# PowerAmplifier_BFU590G.net
KiCad netlist of a schematic drawn in Altium Designer
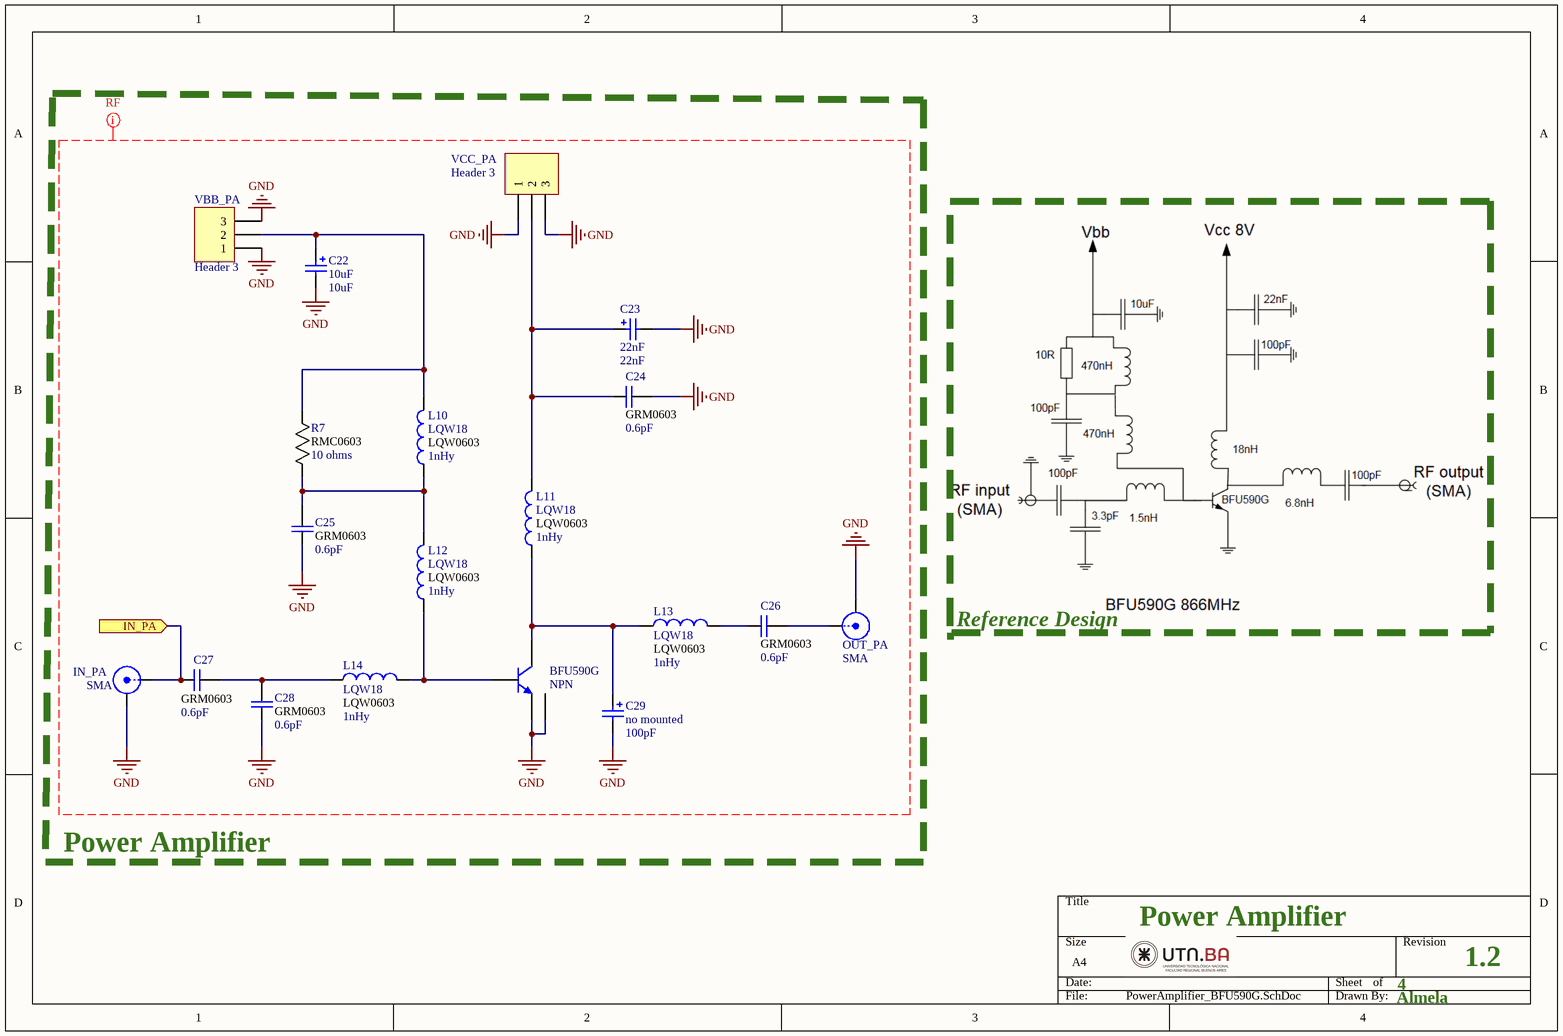
[diagram p0: PowerAmplifier_BFU590G.SchDoc]

(export (version "E")
  (design (tool "Eeschema 10.0.6"))
  (components
    (comp (ref "BFU590G")
      (value "NPN")
      (footprint "SOT223_L")
      (description "NPN Bipolar Transistor")
      (fields (field (name "PUBLISHER") "Altium Limited"))
      (libsource (lib "Radar_RF_EAIII") (part "BFU590G"))
    )
    (comp (ref "C22")
      (value "10uF")
      (footprint "6-0805_N")
      (description "Polarized Capacitor (Axial)")
      (fields (field (name "ALTIUM_VALUE") "10uF") (field (name "PUBLISHER") "Altium Limited"))
      (libsource (lib "Radar_RF_EAIII") (part "Cap Pol2_7"))
    )
    (comp (ref "C23")
      (value "22nF")
      (footprint "6-0805_N")
      (description "Polarized Capacitor (Axial)")
      (fields (field (name "ALTIUM_VALUE") "22nF") (field (name "PUBLISHER") "Altium Limited"))
      (libsource (lib "PCB_Project") (part "Cap Pol2_1"))
    )
    (comp (ref "C24")
      (value "0.6pF")
      (footprint "GRM0603")
      (description "Capacitor GRM18 0603")
      (fields (field (name "Comment") "Cap 0603") (field (name "PUBLISHER") "Altium Limited"))
      (libsource (lib "Radar_RF_EAIII") (part "Cap"))
    )
    (comp (ref "C25")
      (value "0.6pF")
      (footprint "GRM0603")
      (description "Capacitor GRM18 0603")
      (fields (field (name "Comment") "Cap 0603") (field (name "PUBLISHER") "Altium Limited"))
      (libsource (lib "Radar_RF_EAIII") (part "Cap"))
    )
    (comp (ref "C26")
      (value "0.6pF")
      (footprint "GRM0603")
      (description "Capacitor GRM18 0603")
      (fields (field (name "Comment") "Cap 0603") (field (name "PUBLISHER") "Altium Limited"))
      (libsource (lib "Radar_RF_EAIII") (part "Cap"))
    )
    (comp (ref "C27")
      (value "0.6pF")
      (footprint "GRM0603")
      (description "Capacitor GRM18 0603")
      (fields (field (name "Comment") "Cap 0603") (field (name "PUBLISHER") "Altium Limited"))
      (libsource (lib "Radar_RF_EAIII") (part "Cap"))
    )
    (comp (ref "C28")
      (value "0.6pF")
      (footprint "GRM0603")
      (description "Capacitor GRM18 0603")
      (fields (field (name "Comment") "Cap 0603") (field (name "PUBLISHER") "Altium Limited"))
      (libsource (lib "Radar_RF_EAIII") (part "Cap"))
    )
    (comp (ref "C29")
      (value "no mounted")
      (footprint "6-0805_N")
      (description "Polarized Capacitor (Axial)")
      (fields (field (name "ALTIUM_VALUE") "100pF") (field (name "PUBLISHER") "Altium Limited"))
      (libsource (lib "PCB_Project") (part "Cap Pol2_1"))
    )
    (comp (ref "IN_PA")
      (value "SMA")
      (footprint "SMA-142-0701-851_V2")
      (description "SMA Straight Connector")
      (fields (field (name "PUBLISHER") "Altium Limited"))
      (libsource (lib "Radar_RF_EAIII") (part "SMA"))
    )
    (comp (ref "L10")
      (value "LQW18")
      (footprint "INDC1608X100N")
      (description "Ind RF Chip Wirewound 18nH 5% 100MHz 40Q-Factor 550mA 0603 Paper T/R")
      (fields
        (field (name "MP") "LQW18AN18NJ00D")
        (field (name "PARAMETER 1") "LQW0603")
        (field (name "ALTIUM_VALUE") "1nHy")
      )
      (libsource (lib "Radar_RF_EAIII") (part "LQW18"))
    )
    (comp (ref "L11")
      (value "LQW18")
      (footprint "INDC1608X100N")
      (description "Ind RF Chip Wirewound 18nH 5% 100MHz 40Q-Factor 550mA 0603 Paper T/R")
      (fields
        (field (name "MP") "LQW18AN18NJ00D")
        (field (name "PARAMETER 1") "LQW0603")
        (field (name "ALTIUM_VALUE") "1nHy")
      )
      (libsource (lib "Radar_RF_EAIII") (part "LQW18"))
    )
    (comp (ref "L12")
      (value "LQW18")
      (footprint "INDC1608X100N")
      (description "Ind RF Chip Wirewound 18nH 5% 100MHz 40Q-Factor 550mA 0603 Paper T/R")
      (fields
        (field (name "MP") "LQW18AN18NJ00D")
        (field (name "PARAMETER 1") "LQW0603")
        (field (name "ALTIUM_VALUE") "1nHy")
      )
      (libsource (lib "Radar_RF_EAIII") (part "LQW18"))
    )
    (comp (ref "L13")
      (value "LQW18")
      (footprint "INDC1608X100N")
      (description "Ind RF Chip Wirewound 18nH 5% 100MHz 40Q-Factor 550mA 0603 Paper T/R")
      (fields
        (field (name "MP") "LQW18AN18NJ00D")
        (field (name "PARAMETER 1") "LQW0603")
        (field (name "ALTIUM_VALUE") "1nHy")
      )
      (libsource (lib "Radar_RF_EAIII") (part "LQW18"))
    )
    (comp (ref "L14")
      (value "LQW18")
      (footprint "INDC1608X100N")
      (description "Ind RF Chip Wirewound 18nH 5% 100MHz 40Q-Factor 550mA 0603 Paper T/R")
      (fields
        (field (name "MP") "LQW18AN18NJ00D")
        (field (name "PARAMETER 1") "LQW0603")
        (field (name "ALTIUM_VALUE") "1nHy")
      )
      (libsource (lib "Radar_RF_EAIII") (part "LQW18"))
    )
    (comp (ref "OUT_PA")
      (value "SMA")
      (footprint "SMA-142-0701-851_V2")
      (description "SMA Straight Connector")
      (fields (field (name "PUBLISHER") "Altium Limited"))
      (libsource (lib "Radar_RF_EAIII") (part "SMA"))
    )
    (comp (ref "R7")
      (value "10 ohms")
      (footprint "RMC0603")
      (description "Resistor RMC0603")
      (fields (field (name "Comment") "Resistor"))
      (libsource (lib "Radar_RF_EAIII") (part "Resistor"))
    )
    (comp (ref "VBB_PA")
      (value "Header 3")
      (footprint "HDR1X3")
      (description "Header, 3-Pin")
      (fields (field (name "PUBLISHER") "Altium Limited"))
      (libsource (lib "") (part "Header 3_1"))
    )
    (comp (ref "VCC_PA")
      (value "Header 3")
      (footprint "HDR1X3")
      (description "Header, 3-Pin")
      (fields (field (name "PUBLISHER") "Altium Limited"))
      (libsource (lib "Miscellaneous Connectors") (part "Header 3"))
    )
  )
  (nets
    (net (code "1") (name "/IN_PA") (class "Default")
      (node (ref "C27") (pin "1") (pinfunction "1_1") (pintype "passive"))
      (node (ref "IN_PA") (pin "1") (pinfunction "X_1") (pintype "passive"))
    )
    (net (code "2") (name "GND") (class "Default")
      (node (ref "BFU590G") (pin "1") (pinfunction "E_1") (pintype "passive"))
      (node (ref "BFU590G") (pin "3") (pinfunction "E_3") (pintype "passive"))
      (node (ref "C22") (pin "2") (pinfunction "2_2") (pintype "passive"))
      (node (ref "C23") (pin "2") (pinfunction "2_2") (pintype "passive"))
      (node (ref "C24") (pin "2") (pinfunction "2_2") (pintype "passive"))
      (node (ref "C25") (pin "1") (pinfunction "1_1") (pintype "passive"))
      (node (ref "C28") (pin "1") (pinfunction "1_1") (pintype "passive"))
      (node (ref "C29") (pin "2") (pinfunction "2_2") (pintype "passive"))
      (node (ref "IN_PA") (pin "2") (pinfunction "Y_2") (pintype "passive"))
      (node (ref "OUT_PA") (pin "2") (pinfunction "Y_2") (pintype "passive"))
      (node (ref "VBB_PA") (pin "1") (pinfunction "1_1") (pintype "passive"))
      (node (ref "VBB_PA") (pin "3") (pinfunction "3_3") (pintype "passive"))
      (node (ref "VCC_PA") (pin "1") (pinfunction "1_1") (pintype "passive"))
      (node (ref "VCC_PA") (pin "3") (pinfunction "3_3") (pintype "passive"))
    )
    (net (code "3") (name "Net-(BFU590G-B)") (class "Default")
      (node (ref "BFU590G") (pin "2") (pinfunction "B_2") (pintype "passive"))
      (node (ref "L12") (pin "1") (pinfunction "1_1") (pintype "passive"))
      (node (ref "L14") (pin "2") (pinfunction "2_2") (pintype "passive"))
    )
    (net (code "4") (name "Net-(BFU590G-C)") (class "Default")
      (node (ref "BFU590G") (pin "4") (pinfunction "C_4") (pintype "passive"))
      (node (ref "C29") (pin "1") (pinfunction "1_1") (pintype "passive"))
      (node (ref "L11") (pin "1") (pinfunction "1_1") (pintype "passive"))
      (node (ref "L13") (pin "1") (pinfunction "1_1") (pintype "passive"))
    )
    (net (code "5") (name "Net-(C22-Pad1)") (class "Default")
      (node (ref "C22") (pin "1") (pinfunction "1_1") (pintype "passive"))
      (node (ref "L10") (pin "2") (pinfunction "2_2") (pintype "passive"))
      (node (ref "R7") (pin "2") (pinfunction "2_2") (pintype "passive"))
      (node (ref "VBB_PA") (pin "2") (pinfunction "2_2") (pintype "passive"))
    )
    (net (code "6") (name "Net-(C23-Pad1)") (class "Default")
      (node (ref "C23") (pin "1") (pinfunction "1_1") (pintype "passive"))
      (node (ref "C24") (pin "1") (pinfunction "1_1") (pintype "passive"))
      (node (ref "L11") (pin "2") (pinfunction "2_2") (pintype "passive"))
      (node (ref "VCC_PA") (pin "2") (pinfunction "2_2") (pintype "passive"))
    )
    (net (code "7") (name "Net-(C25-Pad2)") (class "Default")
      (node (ref "C25") (pin "2") (pinfunction "2_2") (pintype "passive"))
      (node (ref "L10") (pin "1") (pinfunction "1_1") (pintype "passive"))
      (node (ref "L12") (pin "2") (pinfunction "2_2") (pintype "passive"))
      (node (ref "R7") (pin "1") (pinfunction "1_1") (pintype "passive"))
    )
    (net (code "8") (name "Net-(C26-Pad1)") (class "Default")
      (node (ref "C26") (pin "1") (pinfunction "1_1") (pintype "passive"))
      (node (ref "L13") (pin "2") (pinfunction "2_2") (pintype "passive"))
    )
    (net (code "9") (name "Net-(C27-Pad2)") (class "Default")
      (node (ref "C27") (pin "2") (pinfunction "2_2") (pintype "passive"))
      (node (ref "C28") (pin "2") (pinfunction "2_2") (pintype "passive"))
      (node (ref "L14") (pin "1") (pinfunction "1_1") (pintype "passive"))
    )
    (net (code "10") (name "Net-(OUT_PA-X)") (class "Default")
      (node (ref "C26") (pin "2") (pinfunction "2_2") (pintype "passive"))
      (node (ref "OUT_PA") (pin "1") (pinfunction "X_1") (pintype "passive"))
    )
  )
)
